# 4_Ethernet_PHY.net
KiCad netlist of a schematic drawn in Altium Designer
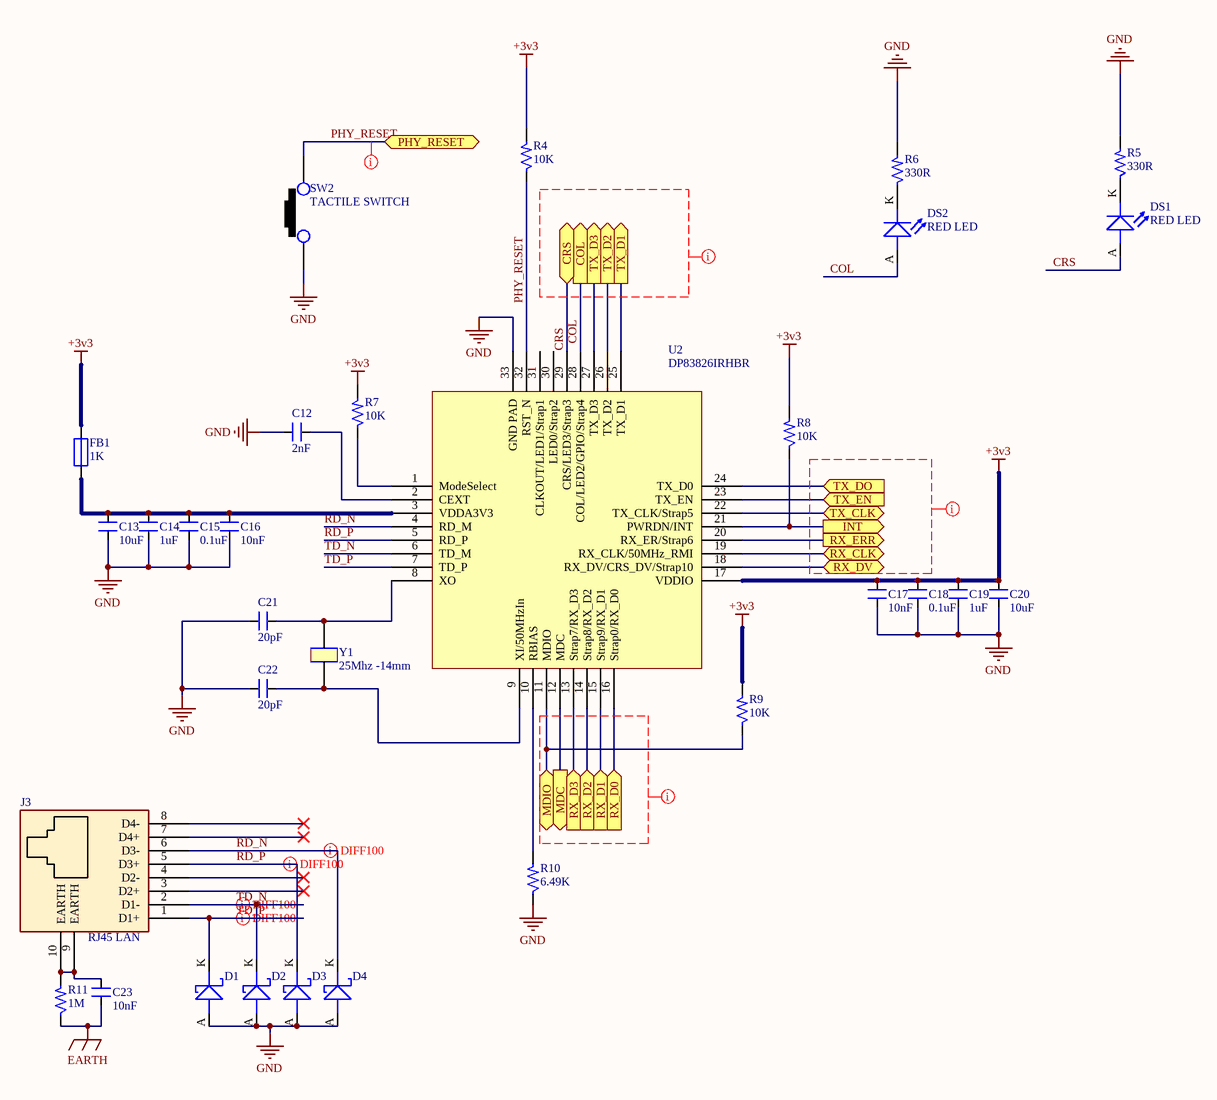
[diagram p0: [4]Ethernet_PHY.SchDoc]

(export (version "E")
  (design (tool "Eeschema 10.0.6"))
  (components
    (comp (ref "C12")
      (value "2nF")
      (footprint "CAP_0805")
      (description "2000pF ±10% 50V Ceramic Capacitor X7R 0805 (2012 Metric)")
      (fields
        (field (name "MANUFACTURER") "Samsung Electro-Mechanics")
        (field (name "MANUFACTURER PART NUMBER") "CL21B202KBANNNC")
      )
      (libsource (lib "ESTEEMPCBLIB") (part "CAP_2nF-50V-10%-0805"))
    )
    (comp (ref "C13")
      (value "10uF")
      (footprint "CAP_1206")
      (description "10µF ±10% 50V Ceramic Capacitor X7R 1206 (3216 Metric)")
      (fields
        (field (name "MANUFACTURER") "KEMET")
        (field (name "MANUFACTURER PART NUMBER") "CL31B106KBHNNNE")
      )
      (libsource (lib "ESTEEMPCBLIB") (part "CAP_10uF-50V-10%-1206"))
    )
    (comp (ref "C14")
      (value "1uF")
      (footprint "CAP_0805")
      (description "1µF ±5% 50V Ceramic Capacitor X7R 0805 (2012 Metric)")
      (fields
        (field (name "MANUFACTURER") "Samsung")
        (field (name "MANUFACTURER PART NUMBER") "CC0805JKX7R9BB105")
      )
      (libsource (lib "ESTEEMPCBLIB") (part "CAP_1uF-50V-5%-0805"))
    )
    (comp (ref "C15")
      (value "0.1uF")
      (footprint "CAP_0805")
      (description "0.1µF ±5% 50V Ceramic Capacitor X7R 0805 (2012 Metric)")
      (fields
        (field (name "MANUFACTURER") "AVX Corporation")
        (field (name "MANUFACTURER PART NUMBER") "08055C104JAT4A")
      )
      (libsource (lib "ESTEEMPCBLIB") (part "CAP_0.1uF-50V-5%-0805"))
    )
    (comp (ref "C16")
      (value "10nF")
      (footprint "CAP_0805")
      (description "10000pF ±10% 50V Ceramic Capacitor X7R 0805 (2012 Metric)")
      (fields
        (field (name "MANUFACTURER") "Samsung")
        (field (name "MANUFACTURER PART NUMBER") "C0805C103K5RECAUTO")
      )
      (libsource (lib "ESTEEMPCBLIB") (part "CAP_10nF-50V-10%-0805"))
    )
    (comp (ref "C17")
      (value "10nF")
      (footprint "CAP_0805")
      (description "10000pF ±10% 50V Ceramic Capacitor X7R 0805 (2012 Metric)")
      (fields
        (field (name "MANUFACTURER") "Samsung")
        (field (name "MANUFACTURER PART NUMBER") "C0805C103K5RECAUTO")
      )
      (libsource (lib "ESTEEMPCBLIB") (part "CAP_10nF-50V-10%-0805"))
    )
    (comp (ref "C18")
      (value "0.1uF")
      (footprint "CAP_0805")
      (description "0.1µF ±5% 50V Ceramic Capacitor X7R 0805 (2012 Metric)")
      (fields
        (field (name "MANUFACTURER") "AVX Corporation")
        (field (name "MANUFACTURER PART NUMBER") "08055C104JAT4A")
      )
      (libsource (lib "ESTEEMPCBLIB") (part "CAP_0.1uF-50V-5%-0805"))
    )
    (comp (ref "C19")
      (value "1uF")
      (footprint "CAP_0805")
      (description "1µF ±5% 50V Ceramic Capacitor X7R 0805 (2012 Metric)")
      (fields
        (field (name "MANUFACTURER") "Samsung")
        (field (name "MANUFACTURER PART NUMBER") "CC0805JKX7R9BB105")
      )
      (libsource (lib "ESTEEMPCBLIB") (part "CAP_1uF-50V-5%-0805"))
    )
    (comp (ref "C20")
      (value "10uF")
      (footprint "CAP_1206")
      (description "10µF ±10% 50V Ceramic Capacitor X7R 1206 (3216 Metric)")
      (fields
        (field (name "MANUFACTURER") "KEMET")
        (field (name "MANUFACTURER PART NUMBER") "CL31B106KBHNNNE")
      )
      (libsource (lib "ESTEEMPCBLIB") (part "CAP_10uF-50V-10%-1206"))
    )
    (comp (ref "C21")
      (value "20pF")
      (footprint "CAP_0805")
      (description "±10% 50V Ceramic Capacitor C0G, NP0 0805 (2012 Metric)")
      (fields
        (field (name "MANUFACTURER") "AVX Corporation")
        (field (name "MANUFACTURER PART NUMBER") "08055A200KAT2A")
      )
      (libsource (lib "ESTEEMPCBLIB") (part "CAP_20pF-50V-10%-0805"))
    )
    (comp (ref "C22")
      (value "20pF")
      (footprint "CAP_0805")
      (description "±10% 50V Ceramic Capacitor C0G, NP0 0805 (2012 Metric)")
      (fields
        (field (name "MANUFACTURER") "AVX Corporation")
        (field (name "MANUFACTURER PART NUMBER") "08055A200KAT2A")
      )
      (libsource (lib "ESTEEMPCBLIB") (part "CAP_20pF-50V-10%-0805"))
    )
    (comp (ref "C23")
      (value "10nF")
      (footprint "CAP_P196_102X287_H332_RAD_TH")
      (description "10000pF ±10% 1000V (1kV) Ceramic Capacitor X7R Radial")
      (fields
        (field (name "MANUFACTURER") "Yageo")
        (field (name "MANUFACTURER PART NUMBER") "RDER73A103K2K1H03B")
      )
      (libsource (lib "ESTEEMPCBLIB") (part "CAP_10nF-1KV-10%-RAD-TH"))
    )
    (comp (ref "D1")
      (value "ESD3V3D9-TP")
      (footprint "DIO_SOD-923")
      (description "TVS DIODE 3.3V 8.8V SOD923")
      (fields (field (name "MANUFACTURER") "Micro Commercial Co"))
      (libsource (lib "ESTEEMPCBLIB") (part "DIO-T_3.3V-8.8V-10A-SOD923"))
    )
    (comp (ref "D2")
      (value "ESD3V3D9-TP")
      (footprint "DIO_SOD-923")
      (description "TVS DIODE 3.3V 8.8V SOD923")
      (fields (field (name "MANUFACTURER") "Micro Commercial Co"))
      (libsource (lib "ESTEEMPCBLIB") (part "DIO-T_3.3V-8.8V-10A-SOD923"))
    )
    (comp (ref "D3")
      (value "ESD3V3D9-TP")
      (footprint "DIO_SOD-923")
      (description "TVS DIODE 3.3V 8.8V SOD923")
      (fields (field (name "MANUFACTURER") "Micro Commercial Co"))
      (libsource (lib "ESTEEMPCBLIB") (part "DIO-T_3.3V-8.8V-10A-SOD923"))
    )
    (comp (ref "D4")
      (value "ESD3V3D9-TP")
      (footprint "DIO_SOD-923")
      (description "TVS DIODE 3.3V 8.8V SOD923")
      (fields (field (name "MANUFACTURER") "Micro Commercial Co"))
      (libsource (lib "ESTEEMPCBLIB") (part "DIO-T_3.3V-8.8V-10A-SOD923"))
    )
    (comp (ref "DS1")
      (value "RED LED")
      (footprint "LED_0805")
      (description "Red 631nm LED Indication - Discrete 2V 0805 (2012 Metric)")
      (fields
        (field (name "MANUFACTURER") "Vishay Lite-On")
        (field (name "MANUFACTURER PART NUMBER") "LTST-C171KRKT")
      )
      (libsource (lib "ESTEEMPCBLIB") (part "LED_RED-2V-20mA-0805"))
    )
    (comp (ref "DS2")
      (value "RED LED")
      (footprint "LED_0805")
      (description "Red 631nm LED Indication - Discrete 2V 0805 (2012 Metric)")
      (fields
        (field (name "MANUFACTURER") "Vishay Lite-On")
        (field (name "MANUFACTURER PART NUMBER") "LTST-C171KRKT")
      )
      (libsource (lib "ESTEEMPCBLIB") (part "LED_RED-2V-20mA-0805"))
    )
    (comp (ref "FB1")
      (value "1K")
      (footprint "IND_0805")
      (description "1 kOhms @ 100MHz 1 Power Line Ferrite Bead 0805 (2012 Metric) 1.6A")
      (fields
        (field (name "MANUFACTURER") "Laird")
        (field (name "MANUFACTURER PART NUMBER") "BLM21SP102SH1D")
      )
      (libsource (lib "ESTEEMPCBLIB") (part "FB_1K-100MHZ-1.6A-0805"))
    )
    (comp (ref "J3")
      (value "RJ45 LAN")
      (footprint "CON10_P106_RJ45_TH_ST")
      (description "8 Pins, 2 Row 2.54mm Pitch, right angle Connector, male")
      (fields
        (field (name "MANUFACTURER") "Assmann")
        (field (name "MANUFACTURER PART NUMBER") "A-2004-2-4-LPS-N-R")
      )
      (libsource (lib "ESTEEMPCBLIB") (part "CON-SKT-RJ_8C8P-RA-TH"))
    )
    (comp (ref "R4")
      (value "10K")
      (footprint "RES_0805")
      (description "10 kOhms ±1% 0.125W, 1/8W Chip Resistor 0805 (2012 Metric) Automotive AEC-Q200 Thick Film")
      (fields (field (name "MANUFACTURER") "CTS") (field (name "MANUFACTURER PART NUMBER") "WR08X1002FTL"))
      (libsource (lib "ESTEEMPCBLIB") (part "RES_10K-0.125W-1%-0805"))
    )
    (comp (ref "R5")
      (value "330R")
      (footprint "RES_0805")
      (description "330 Ohms ±1% 0.125W, 1/8W Chip Resistor 0805 (2012 Metric) Automotive AEC-Q200 Thick Film")
      (fields (field (name "MANUFACTURER") "Walsin") (field (name "MANUFACTURER PART NUMBER") "WR08X3300FTL"))
      (libsource (lib "ESTEEMPCBLIB") (part "RES_330R-0.125W-1%-0805"))
    )
    (comp (ref "R6")
      (value "330R")
      (footprint "RES_0805")
      (description "330 Ohms ±1% 0.125W, 1/8W Chip Resistor 0805 (2012 Metric) Automotive AEC-Q200 Thick Film")
      (fields (field (name "MANUFACTURER") "Walsin") (field (name "MANUFACTURER PART NUMBER") "WR08X3300FTL"))
      (libsource (lib "ESTEEMPCBLIB") (part "RES_330R-0.125W-1%-0805"))
    )
    (comp (ref "R7")
      (value "10K")
      (footprint "RES_0805")
      (description "10 kOhms ±1% 0.125W, 1/8W Chip Resistor 0805 (2012 Metric) Automotive AEC-Q200 Thick Film")
      (fields (field (name "MANUFACTURER") "CTS") (field (name "MANUFACTURER PART NUMBER") "WR08X1002FTL"))
      (libsource (lib "ESTEEMPCBLIB") (part "RES_10K-0.125W-1%-0805"))
    )
    (comp (ref "R8")
      (value "10K")
      (footprint "RES_0805")
      (description "10 kOhms ±1% 0.125W, 1/8W Chip Resistor 0805 (2012 Metric) Automotive AEC-Q200 Thick Film")
      (fields (field (name "MANUFACTURER") "CTS") (field (name "MANUFACTURER PART NUMBER") "WR08X1002FTL"))
      (libsource (lib "ESTEEMPCBLIB") (part "RES_10K-0.125W-1%-0805"))
    )
    (comp (ref "R9")
      (value "10K")
      (footprint "RES_0805")
      (description "10 kOhms ±1% 0.125W, 1/8W Chip Resistor 0805 (2012 Metric) Automotive AEC-Q200 Thick Film")
      (fields (field (name "MANUFACTURER") "CTS") (field (name "MANUFACTURER PART NUMBER") "WR08X1002FTL"))
      (libsource (lib "ESTEEMPCBLIB") (part "RES_10K-0.125W-1%-0805"))
    )
    (comp (ref "R10")
      (value "6.49K")
      (footprint "RES_0805")
      (description "6.49 kOhms ±1% 0.125W, 1/8W Chip Resistor 0805 (2012 Metric) Moisture Resistant Thick Film")
      (fields
        (field (name "MANUFACTURER") "Stackpole Electronics")
        (field (name "MANUFACTURER PART NUMBER") "RC0805FR-076K49L")
      )
      (libsource (lib "ESTEEMPCBLIB") (part "RES_6.49K-0.125W-1%-0805"))
    )
    (comp (ref "R11")
      (value "1M")
      (footprint "RES_0805")
      (description "1 MOhms ±1% 0.125W, 1/8W Chip Resistor 0805 (2012 Metric) Automotive AEC-Q200 Thick Film")
      (fields (field (name "MANUFACTURER") "Walsin") (field (name "MANUFACTURER PART NUMBER") "WR08X1004FTL"))
      (libsource (lib "ESTEEMPCBLIB") (part "RES_1M-0.125W-1%-0805"))
    )
    (comp (ref "SW2")
      (value "TACTILE SWITCH")
      (footprint "SW_342_SMD")
      (description "Tactile Switch SPST-NO Top Actuated Surface Mount")
      (fields
        (field (name "MANUFACTURER") "ITT C&K")
        (field (name "MANUFACTURER PART NUMBER") "RS-282G05A3-SMRT")
      )
      (libsource (lib "ESTEEMPCBLIB") (part "SW1_RS-282G05A3-SMRT-SMD"))
    )
    (comp (ref "U2")
      (value "DP83826IRHBR")
      (footprint "VQFN32_19_218_23X9_SMD")
      (fields (field (name "MANUFACTURER") "Texas Instruments"))
      (libsource (lib "ESTEEMPCBLIB") (part "IC_DP83826IRHBR"))
    )
    (comp (ref "Y1")
      (value "25Mhz -14mm")
      (footprint "XTAL_314_240X47_SMD")
      (description "25MHz ±30ppm Crystal 20pF 30 Ohms HC-49/US")
      (fields
        (field (name "MANUFACTURER") "Abracon")
        (field (name "MANUFACTURER PART NUMBER") "FOXSDLF/250F-20")
      )
      (libsource (lib "ESTEEMPCBLIB") (part "XTAL_25Mhz-FOXSDLF/250F-20"))
    )
  )
  (nets
    (net (code "1") (name "+3v3") (class "Default")
      (node (ref "C17") (pin "2") (pinfunction "2_2") (pintype "passive"))
      (node (ref "C18") (pin "2") (pinfunction "2_2") (pintype "passive"))
      (node (ref "C19") (pin "2") (pinfunction "2_2") (pintype "passive"))
      (node (ref "C20") (pin "2") (pinfunction "2_2") (pintype "passive"))
      (node (ref "FB1") (pin "2") (pinfunction "2_2") (pintype "passive"))
      (node (ref "R4") (pin "2") (pinfunction "2_2") (pintype "passive"))
      (node (ref "R7") (pin "2") (pinfunction "2_2") (pintype "passive"))
      (node (ref "R8") (pin "2") (pinfunction "2_2") (pintype "passive"))
      (node (ref "R9") (pin "2") (pinfunction "2_2") (pintype "passive"))
      (node (ref "U2") (pin "17") (pinfunction "VDDIO_17") (pintype "passive"))
    )
    (net (code "2") (name "/COL") (class "Default")
      (node (ref "DS2") (pin "A") (pinfunction "ANODE_A") (pintype "passive"))
      (node (ref "U2") (pin "28") (pinfunction "COL/LED2/GPIO/Strap4_28") (pintype "passive"))
    )
    (net (code "3") (name "/CRS") (class "Default")
      (node (ref "DS1") (pin "A") (pinfunction "ANODE_A") (pintype "passive"))
      (node (ref "U2") (pin "29") (pinfunction "CRS/LED3/Strap3_29") (pintype "passive"))
    )
    (net (code "4") (name "/INT") (class "Default")
      (node (ref "R8") (pin "1") (pinfunction "1_1") (pintype "passive"))
      (node (ref "U2") (pin "21") (pinfunction "PWRDN/INT_21") (pintype "passive"))
    )
    (net (code "5") (name "/MDC") (class "Default")
      (node (ref "U2") (pin "12") (pinfunction "MDC_12") (pintype "passive"))
    )
    (net (code "6") (name "/MDIO") (class "Default")
      (node (ref "R9") (pin "1") (pinfunction "1_1") (pintype "passive"))
      (node (ref "U2") (pin "11") (pinfunction "MDIO_11") (pintype "passive"))
    )
    (net (code "7") (name "/PHY_RESET") (class "Default")
      (node (ref "R4") (pin "1") (pinfunction "1_1") (pintype "passive"))
      (node (ref "SW2") (pin "2") (pinfunction "2_2") (pintype "passive"))
      (node (ref "U2") (pin "32") (pinfunction "RST_N_32") (pintype "passive"))
    )
    (net (code "8") (name "/RD_N") (class "Default")
      (node (ref "D4") (pin "K") (pinfunction "K_K") (pintype "passive"))
      (node (ref "J3") (pin "6") (pinfunction "D3-_6") (pintype "passive"))
      (node (ref "U2") (pin "4") (pinfunction "RD_M_4") (pintype "passive"))
    )
    (net (code "9") (name "/RD_P") (class "Default")
      (node (ref "D3") (pin "K") (pinfunction "K_K") (pintype "passive"))
      (node (ref "J3") (pin "5") (pinfunction "D3+_5") (pintype "passive"))
      (node (ref "U2") (pin "5") (pinfunction "RD_P_5") (pintype "passive"))
    )
    (net (code "10") (name "/RX_CLK") (class "Default")
      (node (ref "U2") (pin "19") (pinfunction "RX_CLK/50MHz_RMI_19") (pintype "passive"))
    )
    (net (code "11") (name "/RX_D0") (class "Default")
      (node (ref "U2") (pin "16") (pinfunction "Strap0/RX_D0_16") (pintype "passive"))
    )
    (net (code "12") (name "/RX_D1") (class "Default")
      (node (ref "U2") (pin "15") (pinfunction "Strap9/RX_D1_15") (pintype "passive"))
    )
    (net (code "13") (name "/RX_D2") (class "Default")
      (node (ref "U2") (pin "14") (pinfunction "Strap8/RX_D2_14") (pintype "passive"))
    )
    (net (code "14") (name "/RX_D3") (class "Default")
      (node (ref "U2") (pin "13") (pinfunction "Strap7/RX_D3_13") (pintype "passive"))
    )
    (net (code "15") (name "/RX_DV") (class "Default")
      (node (ref "U2") (pin "18") (pinfunction "RX_DV/CRS_DV/Strap10_18") (pintype "passive"))
    )
    (net (code "16") (name "/RX_ERR") (class "Default")
      (node (ref "U2") (pin "20") (pinfunction "RX_ER/Strap6_20") (pintype "passive"))
    )
    (net (code "17") (name "/TD_N") (class "Default")
      (node (ref "D2") (pin "K") (pinfunction "K_K") (pintype "passive"))
      (node (ref "J3") (pin "2") (pinfunction "D1-_2") (pintype "passive"))
      (node (ref "U2") (pin "6") (pinfunction "TD_M_6") (pintype "passive"))
    )
    (net (code "18") (name "/TD_P") (class "Default")
      (node (ref "D1") (pin "K") (pinfunction "K_K") (pintype "passive"))
      (node (ref "J3") (pin "1") (pinfunction "D1+_1") (pintype "passive"))
      (node (ref "U2") (pin "7") (pinfunction "TD_P_7") (pintype "passive"))
    )
    (net (code "19") (name "/TX_CLK") (class "Default")
      (node (ref "U2") (pin "22") (pinfunction "TX_CLK/Strap5_22") (pintype "passive"))
    )
    (net (code "20") (name "/TX_D1") (class "Default")
      (node (ref "U2") (pin "25") (pinfunction "TX_D1_25") (pintype "passive"))
    )
    (net (code "21") (name "/TX_D2") (class "Default")
      (node (ref "U2") (pin "26") (pinfunction "TX_D2_26") (pintype "passive"))
    )
    (net (code "22") (name "/TX_D3") (class "Default")
      (node (ref "U2") (pin "27") (pinfunction "TX_D3_27") (pintype "passive"))
    )
    (net (code "23") (name "/TX_DO") (class "Default")
      (node (ref "U2") (pin "24") (pinfunction "TX_D0_24") (pintype "passive"))
    )
    (net (code "24") (name "/TX_EN") (class "Default")
      (node (ref "U2") (pin "23") (pinfunction "TX_EN_23") (pintype "passive"))
    )
    (net (code "25") (name "EARTH") (class "Default")
      (node (ref "C23") (pin "1") (pinfunction "1_1") (pintype "passive"))
      (node (ref "R11") (pin "1") (pinfunction "1_1") (pintype "passive"))
    )
    (net (code "26") (name "GND") (class "Default")
      (node (ref "C12") (pin "1") (pinfunction "1_1") (pintype "passive"))
      (node (ref "C13") (pin "1") (pinfunction "1_1") (pintype "passive"))
      (node (ref "C14") (pin "1") (pinfunction "1_1") (pintype "passive"))
      (node (ref "C15") (pin "1") (pinfunction "1_1") (pintype "passive"))
      (node (ref "C16") (pin "1") (pinfunction "1_1") (pintype "passive"))
      (node (ref "C17") (pin "1") (pinfunction "1_1") (pintype "passive"))
      (node (ref "C18") (pin "1") (pinfunction "1_1") (pintype "passive"))
      (node (ref "C19") (pin "1") (pinfunction "1_1") (pintype "passive"))
      (node (ref "C20") (pin "1") (pinfunction "1_1") (pintype "passive"))
      (node (ref "C21") (pin "1") (pinfunction "1_1") (pintype "passive"))
      (node (ref "C22") (pin "1") (pinfunction "1_1") (pintype "passive"))
      (node (ref "D1") (pin "A") (pinfunction "A_A") (pintype "passive"))
      (node (ref "D2") (pin "A") (pinfunction "A_A") (pintype "passive"))
      (node (ref "D3") (pin "A") (pinfunction "A_A") (pintype "passive"))
      (node (ref "D4") (pin "A") (pinfunction "A_A") (pintype "passive"))
      (node (ref "R10") (pin "1") (pinfunction "1_1") (pintype "passive"))
      (node (ref "R5") (pin "2") (pinfunction "2_2") (pintype "passive"))
      (node (ref "R6") (pin "2") (pinfunction "2_2") (pintype "passive"))
      (node (ref "SW2") (pin "1") (pinfunction "1_1") (pintype "passive"))
      (node (ref "U2") (pin "33") (pinfunction "GND_PAD_33") (pintype "passive"))
    )
    (net (code "27") (name "Net-(C23-Pad2)") (class "Default")
      (node (ref "C23") (pin "2") (pinfunction "2_2") (pintype "passive"))
      (node (ref "J3") (pin "10") (pinfunction "EARTH_10") (pintype "passive"))
      (node (ref "J3") (pin "9") (pinfunction "EARTH_9") (pintype "passive"))
      (node (ref "R11") (pin "2") (pinfunction "2_2") (pintype "passive"))
    )
    (net (code "28") (name "Net-(DS1-CATHODE)") (class "Default")
      (node (ref "DS1") (pin "K") (pinfunction "CATHODE_K") (pintype "passive"))
      (node (ref "R5") (pin "1") (pinfunction "1_1") (pintype "passive"))
    )
    (net (code "29") (name "Net-(DS2-CATHODE)") (class "Default")
      (node (ref "DS2") (pin "K") (pinfunction "CATHODE_K") (pintype "passive"))
      (node (ref "R6") (pin "1") (pinfunction "1_1") (pintype "passive"))
    )
    (net (code "30") (name "Net-(U2-CEXT)") (class "Default")
      (node (ref "C12") (pin "2") (pinfunction "2_2") (pintype "passive"))
      (node (ref "U2") (pin "2") (pinfunction "CEXT_2") (pintype "passive"))
    )
    (net (code "31") (name "Net-(U2-ModeSelect)") (class "Default")
      (node (ref "R7") (pin "1") (pinfunction "1_1") (pintype "passive"))
      (node (ref "U2") (pin "1") (pinfunction "ModeSelect_1") (pintype "passive"))
    )
    (net (code "32") (name "Net-(U2-RBIAS)") (class "Default")
      (node (ref "R10") (pin "2") (pinfunction "2_2") (pintype "passive"))
      (node (ref "U2") (pin "10") (pinfunction "RBIAS_10") (pintype "passive"))
    )
    (net (code "33") (name "Net-(U2-VDDA3V3)") (class "Default")
      (node (ref "C13") (pin "2") (pinfunction "2_2") (pintype "passive"))
      (node (ref "C14") (pin "2") (pinfunction "2_2") (pintype "passive"))
      (node (ref "C15") (pin "2") (pinfunction "2_2") (pintype "passive"))
      (node (ref "C16") (pin "2") (pinfunction "2_2") (pintype "passive"))
      (node (ref "FB1") (pin "1") (pinfunction "1_1") (pintype "passive"))
      (node (ref "U2") (pin "3") (pinfunction "VDDA3V3_3") (pintype "passive"))
    )
    (net (code "34") (name "Net-(U2-XI{slash}50MHzIn)") (class "Default")
      (node (ref "C22") (pin "2") (pinfunction "2_2") (pintype "passive"))
      (node (ref "U2") (pin "9") (pinfunction "XI/50MHzIn_9") (pintype "passive"))
      (node (ref "Y1") (pin "1") (pinfunction "1_1") (pintype "passive"))
    )
    (net (code "35") (name "Net-(U2-XO)") (class "Default")
      (node (ref "C21") (pin "2") (pinfunction "2_2") (pintype "passive"))
      (node (ref "U2") (pin "8") (pinfunction "XO_8") (pintype "passive"))
      (node (ref "Y1") (pin "2") (pinfunction "2_2") (pintype "passive"))
    )
    (net (code "36") (name "unconnected-(J3-D2+-Pad3)") (class "Default")
      (node (ref "J3") (pin "3") (pinfunction "D2+_3") (pintype "passive+no_connect"))
    )
    (net (code "37") (name "unconnected-(J3-D2--Pad4)") (class "Default")
      (node (ref "J3") (pin "4") (pinfunction "D2-_4") (pintype "passive+no_connect"))
    )
    (net (code "38") (name "unconnected-(J3-D4+-Pad7)") (class "Default")
      (node (ref "J3") (pin "7") (pinfunction "D4+_7") (pintype "passive+no_connect"))
    )
    (net (code "39") (name "unconnected-(J3-D4--Pad8)") (class "Default")
      (node (ref "J3") (pin "8") (pinfunction "D4-_8") (pintype "passive+no_connect"))
    )
    (net (code "40") (name "unconnected-(U2-CLKOUT{slash}LED1{slash}Strap1-Pad31)") (class "Default")
      (node (ref "U2") (pin "31") (pinfunction "CLKOUT/LED1/Strap1_31") (pintype "passive"))
    )
    (net (code "41") (name "unconnected-(U2-LED0{slash}Strap2-Pad30)") (class "Default")
      (node (ref "U2") (pin "30") (pinfunction "LED0/Strap2_30") (pintype "passive"))
    )
  )
)
